# 8_gate_driver.net
KiCad netlist of a schematic drawn in Altium Designer
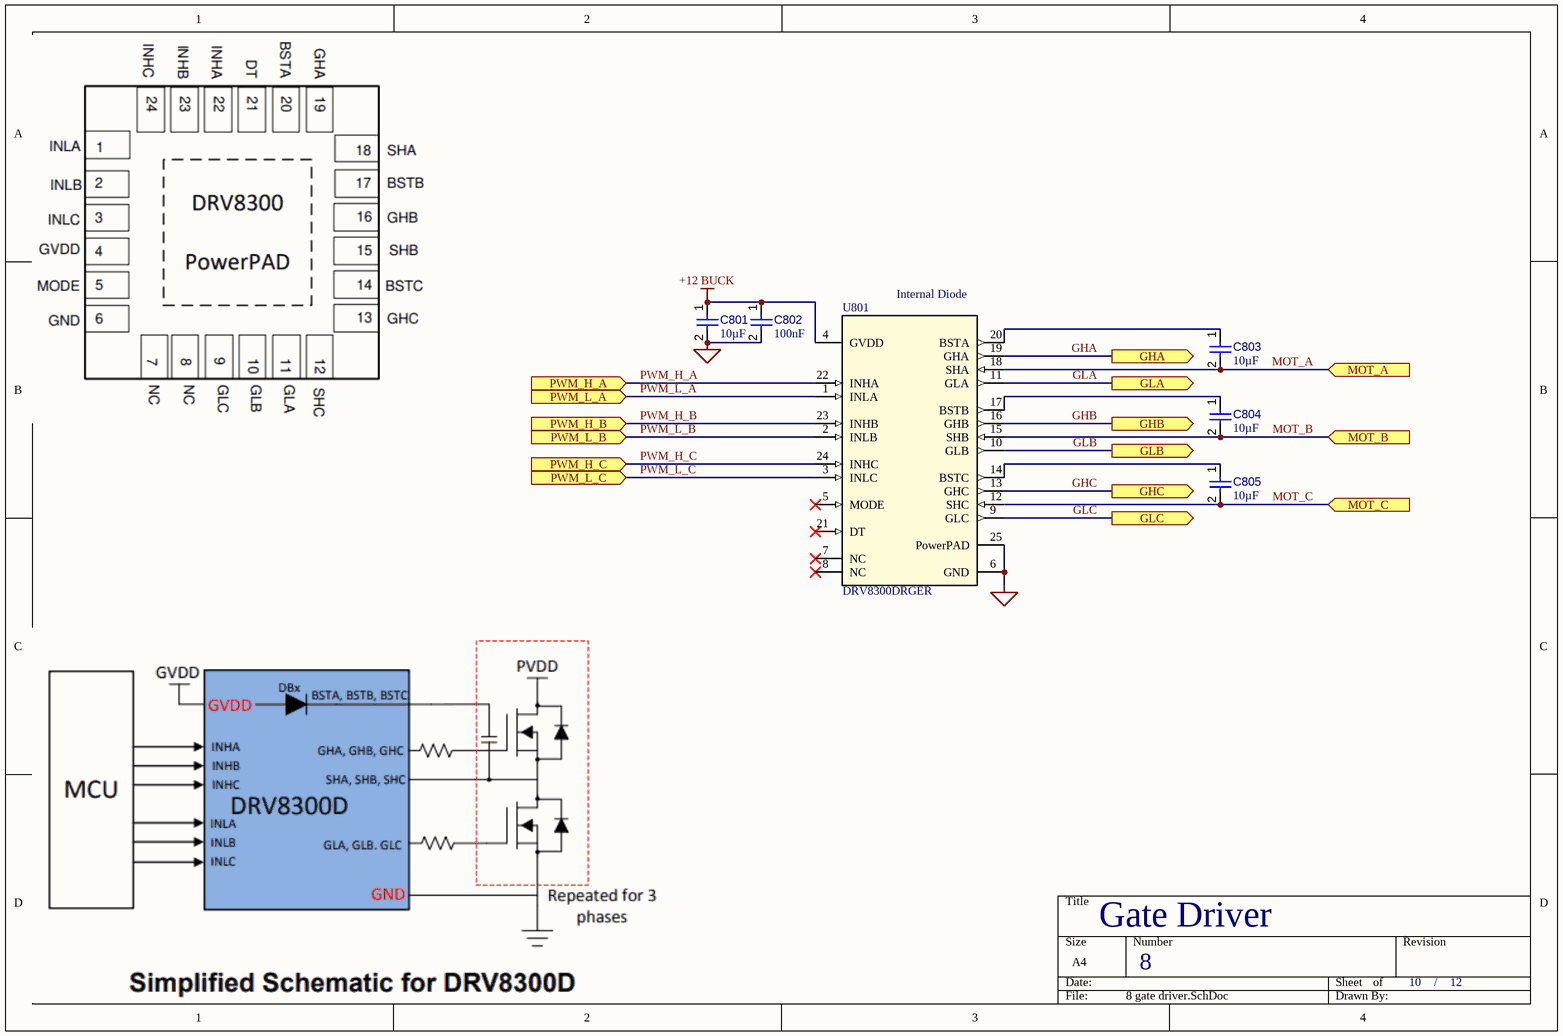
[diagram p0: 8 gate driver.SchDoc]

(export (version "E")
  (design (tool "Eeschema 10.0.6"))
  (components
    (comp (ref "C801")
      (value "10µF")
      (footprint "CAPC0603(1608)100_L")
      (description "Chip Capacitor, 10µF +/-20%, 10V, 0603, Thickness 1 mm")
      (fields (field (name "TOLERANCE") "10%") (field (name "Comment") "Capacitor 10µF +/-20% 10V 0603"))
      (libsource (lib "UBC Uncrewed Aircraft Systems") (part "CAP-NP-2"))
    )
    (comp (ref "C802")
      (value "100nF")
      (footprint "CAPC0402(1005)60_L")
      (description "Chip Capacitor, 100nF +/-20%, 25V, 0402, Thickness 0.6 mm")
      (fields (field (name "TOLERANCE") "10%") (field (name "Comment") "Capacitor 100nF +/-20% 25V 0402"))
      (libsource (lib "UBC Uncrewed Aircraft Systems") (part "CAP-NP-2"))
    )
    (comp (ref "C803")
      (value "10µF")
      (footprint "CAPC0603(1608)100_L")
      (description "Chip Capacitor, 10µF +/-20%, 10V, 0603, Thickness 1 mm")
      (fields (field (name "TOLERANCE") "10%") (field (name "Comment") "Capacitor 10µF +/-20% 10V 0603"))
      (libsource (lib "UBC Uncrewed Aircraft Systems") (part "CAP-NP-2"))
    )
    (comp (ref "C804")
      (value "10µF")
      (footprint "CAPC0603(1608)100_L")
      (description "Chip Capacitor, 10µF +/-20%, 10V, 0603, Thickness 1 mm")
      (fields (field (name "TOLERANCE") "10%") (field (name "Comment") "Capacitor 10µF +/-20% 10V 0603"))
      (libsource (lib "UBC Uncrewed Aircraft Systems") (part "CAP-NP-2"))
    )
    (comp (ref "C805")
      (value "10µF")
      (footprint "CAPC0603(1608)100_L")
      (description "Chip Capacitor, 10µF +/-20%, 10V, 0603, Thickness 1 mm")
      (fields (field (name "TOLERANCE") "10%") (field (name "Comment") "Capacitor 10µF +/-20% 10V 0603"))
      (libsource (lib "UBC Uncrewed Aircraft Systems") (part "CAP-NP-2"))
    )
    (comp (ref "U801")
      (value "DRV8300DRGER")
      (footprint "RGE0024B-MFG")
      (description "No Description Available")
      (libsource (lib "DRV8300DRGER") (part "DRV8300DRGER"))
    )
  )
  (nets
    (net (code "1") (name "+12 BUCK") (class "Default")
      (node (ref "C801") (pin "1") (pinfunction "1_1") (pintype "passive"))
      (node (ref "C802") (pin "1") (pinfunction "1_1") (pintype "passive"))
      (node (ref "U801") (pin "4") (pinfunction "GVDD_4") (pintype "power_in"))
    )
    (net (code "2") (name "/GHA") (class "Default")
      (node (ref "U801") (pin "19") (pinfunction "GHA_19") (pintype "output"))
    )
    (net (code "3") (name "/GHB") (class "Default")
      (node (ref "U801") (pin "16") (pinfunction "GHB_16") (pintype "output"))
    )
    (net (code "4") (name "/GHC") (class "Default")
      (node (ref "U801") (pin "13") (pinfunction "GHC_13") (pintype "output"))
    )
    (net (code "5") (name "/GLA") (class "Default")
      (node (ref "U801") (pin "11") (pinfunction "GLA_11") (pintype "output"))
    )
    (net (code "6") (name "/GLB") (class "Default")
      (node (ref "U801") (pin "10") (pinfunction "GLB_10") (pintype "output"))
    )
    (net (code "7") (name "/GLC") (class "Default")
      (node (ref "U801") (pin "9") (pinfunction "GLC_9") (pintype "output"))
    )
    (net (code "8") (name "/MOT_A") (class "Default")
      (node (ref "C803") (pin "2") (pinfunction "2_2") (pintype "passive"))
      (node (ref "U801") (pin "18") (pinfunction "SHA_18") (pintype "input"))
    )
    (net (code "9") (name "/MOT_B") (class "Default")
      (node (ref "C804") (pin "2") (pinfunction "2_2") (pintype "passive"))
      (node (ref "U801") (pin "15") (pinfunction "SHB_15") (pintype "input"))
    )
    (net (code "10") (name "/MOT_C") (class "Default")
      (node (ref "C805") (pin "2") (pinfunction "2_2") (pintype "passive"))
      (node (ref "U801") (pin "12") (pinfunction "SHC_12") (pintype "input"))
    )
    (net (code "11") (name "/PWM_H_A") (class "Default")
      (node (ref "U801") (pin "22") (pinfunction "INHA_22") (pintype "input"))
    )
    (net (code "12") (name "/PWM_H_B") (class "Default")
      (node (ref "U801") (pin "23") (pinfunction "INHB_23") (pintype "input"))
    )
    (net (code "13") (name "/PWM_H_C") (class "Default")
      (node (ref "U801") (pin "24") (pinfunction "INHC_24") (pintype "input"))
    )
    (net (code "14") (name "/PWM_L_A") (class "Default")
      (node (ref "U801") (pin "1") (pinfunction "INLA_1") (pintype "input"))
    )
    (net (code "15") (name "/PWM_L_B") (class "Default")
      (node (ref "U801") (pin "2") (pinfunction "INLB_2") (pintype "input"))
    )
    (net (code "16") (name "/PWM_L_C") (class "Default")
      (node (ref "U801") (pin "3") (pinfunction "INLC_3") (pintype "input"))
    )
    (net (code "17") (name "Net-(U801-BSTA)") (class "Default")
      (node (ref "C803") (pin "1") (pinfunction "1_1") (pintype "passive"))
      (node (ref "U801") (pin "20") (pinfunction "BSTA_20") (pintype "output"))
    )
    (net (code "18") (name "Net-(U801-BSTB)") (class "Default")
      (node (ref "C804") (pin "1") (pinfunction "1_1") (pintype "passive"))
      (node (ref "U801") (pin "17") (pinfunction "BSTB_17") (pintype "output"))
    )
    (net (code "19") (name "Net-(U801-BSTC)") (class "Default")
      (node (ref "C805") (pin "1") (pinfunction "1_1") (pintype "passive"))
      (node (ref "U801") (pin "14") (pinfunction "BSTC_14") (pintype "output"))
    )
    (net (code "20") (name "PGND") (class "Default")
      (node (ref "C801") (pin "2") (pinfunction "2_2") (pintype "passive"))
      (node (ref "C802") (pin "2") (pinfunction "2_2") (pintype "passive"))
      (node (ref "U801") (pin "25") (pinfunction "PowerPAD_25") (pintype "power_in"))
      (node (ref "U801") (pin "6") (pinfunction "GND_6") (pintype "power_in"))
    )
    (net (code "21") (name "unconnected-(U801-DT-Pad21)") (class "Default")
      (node (ref "U801") (pin "21") (pinfunction "DT_21") (pintype "input+no_connect"))
    )
    (net (code "22") (name "unconnected-(U801-MODE-Pad5)") (class "Default")
      (node (ref "U801") (pin "5") (pinfunction "MODE_5") (pintype "input+no_connect"))
    )
    (net (code "23") (name "unconnected-(U801-NC-Pad7)") (class "Default")
      (node (ref "U801") (pin "7") (pinfunction "NC_7") (pintype "passive+no_connect"))
    )
    (net (code "24") (name "unconnected-(U801-NC-Pad8)") (class "Default")
      (node (ref "U801") (pin "8") (pinfunction "NC_8") (pintype "passive+no_connect"))
    )
  )
)
